# Spectacle_Button_Board.net
KiCad netlist of a schematic drawn in EAGLE
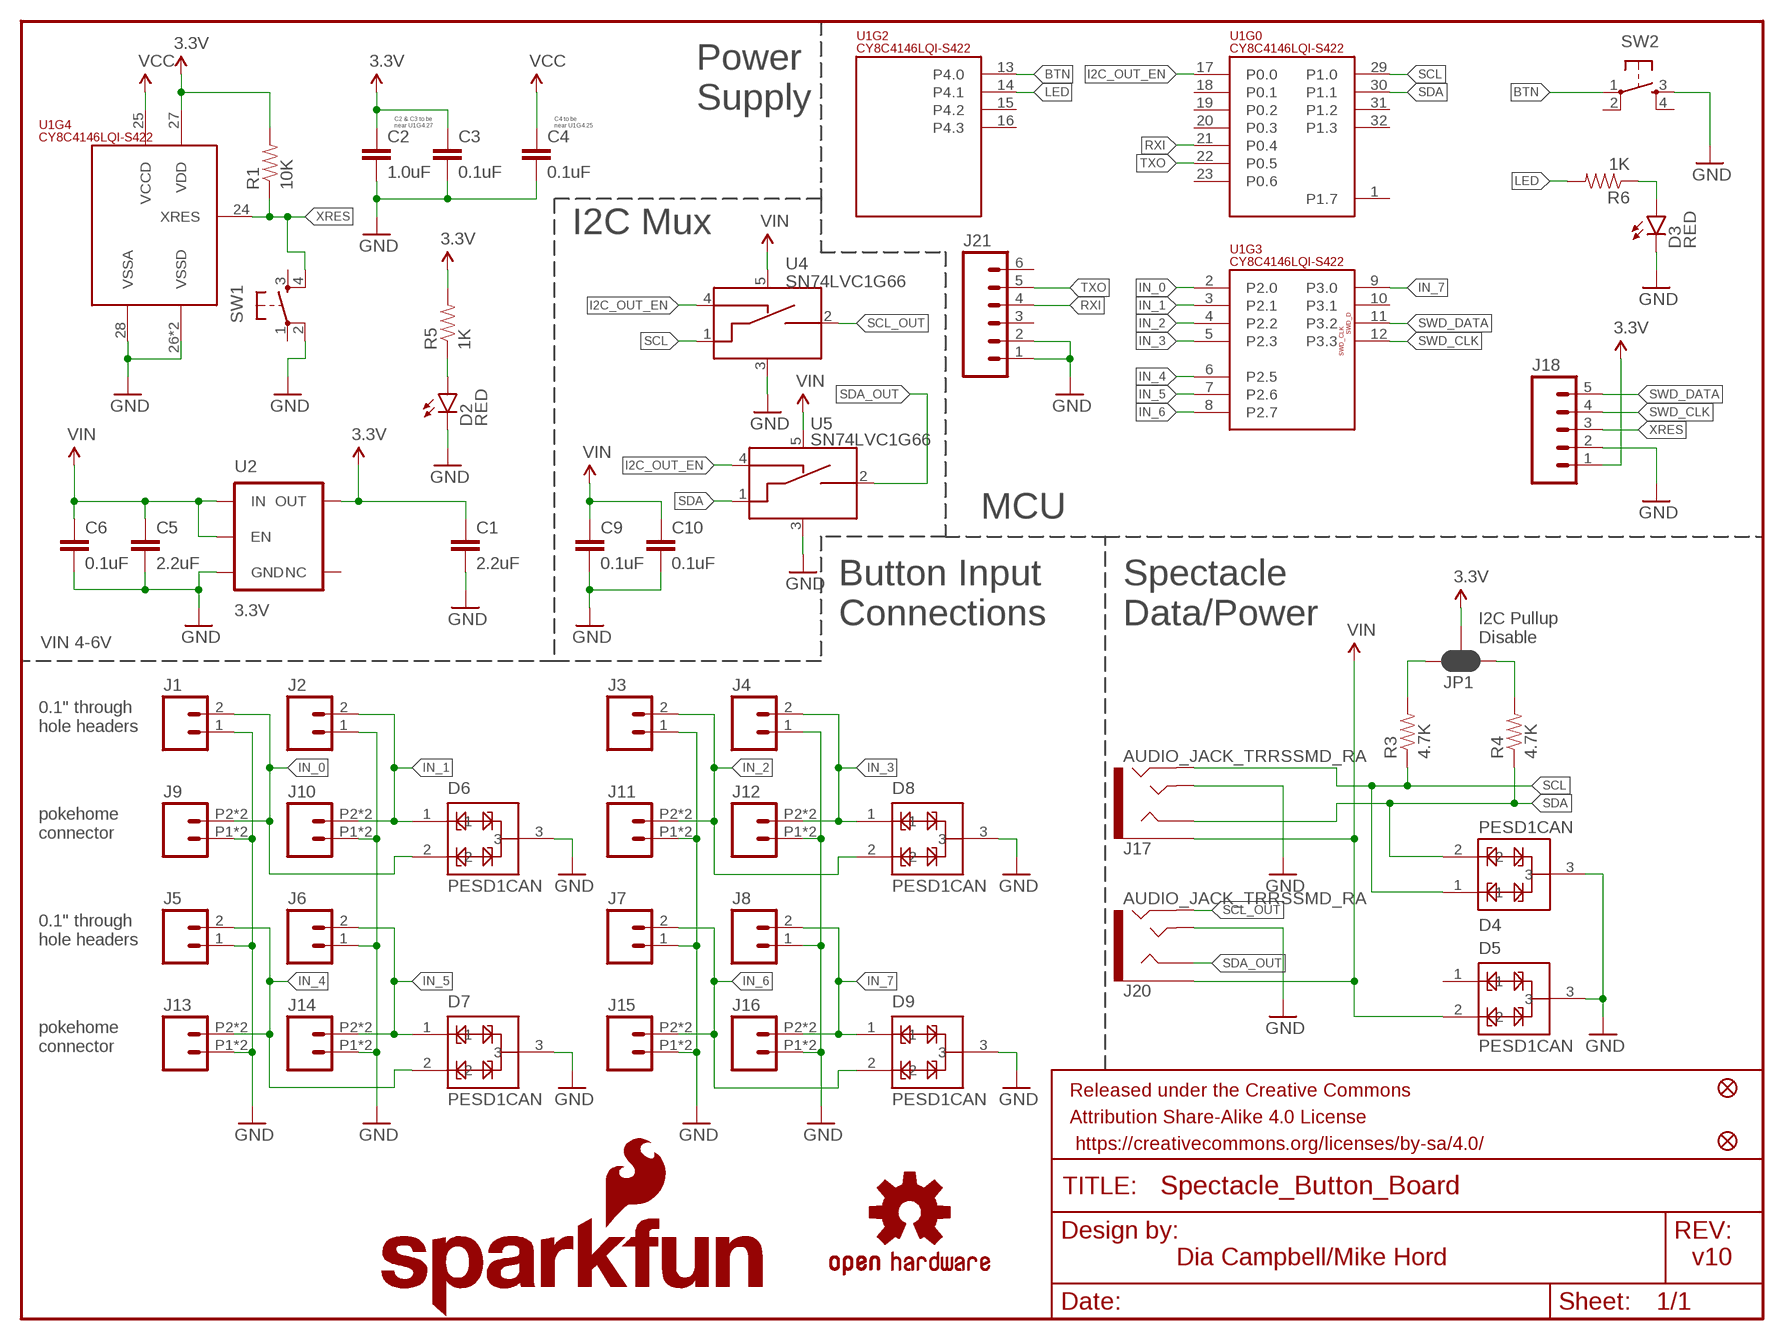
[diagram p0: schematic, sheet 1]

(export (version "E")
  (design (tool "Eeschema 10.0.6"))
  (components
    (comp (ref "C1")
      (value "2.2uF")
      (footprint "eagle-import:0603-CAP")
      (libsource (lib "eagle-import") (part "2.2UF-10V-20%(0603)"))
    )
    (comp (ref "C2")
      (value "1.0uF")
      (footprint "eagle-import:0402-CAP")
      (libsource (lib "eagle-import") (part "1.0UF-16V-10%(0402)"))
    )
    (comp (ref "C3")
      (value "0.1uF")
      (footprint "eagle-import:0402-CAP")
      (libsource (lib "eagle-import") (part "0.1UF-16V(+-10%)(0402)"))
    )
    (comp (ref "C4")
      (value "0.1uF")
      (footprint "eagle-import:0402-CAP")
      (libsource (lib "eagle-import") (part "0.1UF-16V(+-10%)(0402)"))
    )
    (comp (ref "C5")
      (value "2.2uF")
      (footprint "eagle-import:0603-CAP")
      (libsource (lib "eagle-import") (part "2.2UF-10V-20%(0603)"))
    )
    (comp (ref "C6")
      (value "0.1uF")
      (footprint "eagle-import:0402-CAP")
      (libsource (lib "eagle-import") (part "0.1UF-16V(+-10%)(0402)"))
    )
    (comp (ref "C9")
      (value "0.1uF")
      (footprint "eagle-import:0402-CAP")
      (libsource (lib "eagle-import") (part "0.1UF-16V(+-10%)(0402)"))
    )
    (comp (ref "C10")
      (value "0.1uF")
      (footprint "eagle-import:0402-CAP")
      (libsource (lib "eagle-import") (part "0.1UF-16V(+-10%)(0402)"))
    )
    (comp (ref "D2")
      (value "RED")
      (footprint "eagle-import:LED-0603")
      (libsource (lib "eagle-import") (part "LED-RED0603"))
    )
    (comp (ref "D3")
      (value "RED")
      (footprint "eagle-import:LED-0603")
      (libsource (lib "eagle-import") (part "LED-RED0603"))
    )
    (comp (ref "D4")
      (value "PESD1CAN")
      (footprint "eagle-import:SOT23-3")
      (libsource (lib "eagle-import") (part "PESD1CAN"))
    )
    (comp (ref "D5")
      (value "PESD1CAN")
      (footprint "eagle-import:SOT23-3")
      (libsource (lib "eagle-import") (part "PESD1CAN"))
    )
    (comp (ref "D6")
      (value "PESD1CAN")
      (footprint "eagle-import:SOT23-3")
      (libsource (lib "eagle-import") (part "PESD1CAN"))
    )
    (comp (ref "D7")
      (value "PESD1CAN")
      (footprint "eagle-import:SOT23-3")
      (libsource (lib "eagle-import") (part "PESD1CAN"))
    )
    (comp (ref "D8")
      (value "PESD1CAN")
      (footprint "eagle-import:SOT23-3")
      (libsource (lib "eagle-import") (part "PESD1CAN"))
    )
    (comp (ref "D9")
      (value "PESD1CAN")
      (footprint "eagle-import:SOT23-3")
      (libsource (lib "eagle-import") (part "PESD1CAN"))
    )
    (comp (ref "FD1")
      (value "FIDUCIALUFIDUCIAL")
      (footprint "eagle-import:MICRO-FIDUCIAL")
      (libsource (lib "eagle-import") (part "FIDUCIALUFIDUCIAL"))
    )
    (comp (ref "FD2")
      (value "FIDUCIALUFIDUCIAL")
      (footprint "eagle-import:MICRO-FIDUCIAL")
      (libsource (lib "eagle-import") (part "FIDUCIALUFIDUCIAL"))
    )
    (comp (ref "FRAME1")
      (value "FRAME-LETTER")
      (footprint "eagle-import:CREATIVE_COMMONS")
      (libsource (lib "eagle-import") (part "FRAME-LETTER"))
    )
    (comp (ref "J1")
      (value "M02PTH")
      (footprint "eagle-import:1X02")
      (libsource (lib "eagle-import") (part "M02PTH"))
    )
    (comp (ref "J2")
      (value "M02PTH")
      (footprint "eagle-import:1X02")
      (libsource (lib "eagle-import") (part "M02PTH"))
    )
    (comp (ref "J3")
      (value "M02PTH")
      (footprint "eagle-import:1X02")
      (libsource (lib "eagle-import") (part "M02PTH"))
    )
    (comp (ref "J4")
      (value "M02PTH")
      (footprint "eagle-import:1X02")
      (libsource (lib "eagle-import") (part "M02PTH"))
    )
    (comp (ref "J5")
      (value "M02PTH")
      (footprint "eagle-import:1X02")
      (libsource (lib "eagle-import") (part "M02PTH"))
    )
    (comp (ref "J6")
      (value "M02PTH")
      (footprint "eagle-import:1X02")
      (libsource (lib "eagle-import") (part "M02PTH"))
    )
    (comp (ref "J7")
      (value "M02PTH")
      (footprint "eagle-import:1X02")
      (libsource (lib "eagle-import") (part "M02PTH"))
    )
    (comp (ref "J8")
      (value "M02PTH")
      (footprint "eagle-import:1X02")
      (libsource (lib "eagle-import") (part "M02PTH"))
    )
    (comp (ref "J9")
      (value "M02SMALL_POKEHOME")
      (footprint "eagle-import:1X02_POKEHOME")
      (libsource (lib "eagle-import") (part "M02SMALL_POKEHOME"))
    )
    (comp (ref "J10")
      (value "M02SMALL_POKEHOME")
      (footprint "eagle-import:1X02_POKEHOME")
      (libsource (lib "eagle-import") (part "M02SMALL_POKEHOME"))
    )
    (comp (ref "J11")
      (value "M02SMALL_POKEHOME")
      (footprint "eagle-import:1X02_POKEHOME")
      (libsource (lib "eagle-import") (part "M02SMALL_POKEHOME"))
    )
    (comp (ref "J12")
      (value "M02SMALL_POKEHOME")
      (footprint "eagle-import:1X02_POKEHOME")
      (libsource (lib "eagle-import") (part "M02SMALL_POKEHOME"))
    )
    (comp (ref "J13")
      (value "M02SMALL_POKEHOME")
      (footprint "eagle-import:1X02_POKEHOME")
      (libsource (lib "eagle-import") (part "M02SMALL_POKEHOME"))
    )
    (comp (ref "J14")
      (value "M02SMALL_POKEHOME")
      (footprint "eagle-import:1X02_POKEHOME")
      (libsource (lib "eagle-import") (part "M02SMALL_POKEHOME"))
    )
    (comp (ref "J15")
      (value "M02SMALL_POKEHOME")
      (footprint "eagle-import:1X02_POKEHOME")
      (libsource (lib "eagle-import") (part "M02SMALL_POKEHOME"))
    )
    (comp (ref "J16")
      (value "M02SMALL_POKEHOME")
      (footprint "eagle-import:1X02_POKEHOME")
      (libsource (lib "eagle-import") (part "M02SMALL_POKEHOME"))
    )
    (comp (ref "J17")
      (value "AUDIO_JACK_TRRSSMD_RA")
      (footprint "eagle-import:AUDIO_JACK_3.5MM_TRRS_SMD_RA")
      (libsource (lib "eagle-import") (part "AUDIO_JACK_TRRSSMD_RA"))
    )
    (comp (ref "J18")
      (value "M05NO_SILK")
      (footprint "eagle-import:1X05_NO_SILK")
      (libsource (lib "eagle-import") (part "M05NO_SILK"))
    )
    (comp (ref "J20")
      (value "AUDIO_JACK_TRRSSMD_RA")
      (footprint "eagle-import:AUDIO_JACK_3.5MM_TRRS_SMD_RA")
      (libsource (lib "eagle-import") (part "AUDIO_JACK_TRRSSMD_RA"))
    )
    (comp (ref "J21")
      (value "M06NO_SILK_NO_POP")
      (footprint "eagle-import:1X06_NO_SILK")
      (libsource (lib "eagle-import") (part "M06NO_SILK_NO_POP"))
    )
    (comp (ref "JP1")
      (value "JUMPER-PAD-3-NC_BY_PASTE")
      (footprint "eagle-import:PAD-JUMPER-3-NC_BY_PASTE_YES_SILK_FULL_BOX")
      (libsource (lib "eagle-import") (part "JUMPER-PAD-3-NC_BY_PASTE"))
    )
    (comp (ref "LOGO1")
      (value "OSHW-LOGOM")
      (footprint "eagle-import:OSHW-LOGO-M")
      (libsource (lib "eagle-import") (part "OSHW-LOGOM"))
    )
    (comp (ref "LOGO2")
      (value "SFE_LOGO_NAME_FLAME.1_INCH")
      (footprint "eagle-import:SFE_LOGO_NAME_FLAME_.1")
      (libsource (lib "eagle-import") (part "SFE_LOGO_NAME_FLAME.1_INCH"))
    )
    (comp (ref "R1")
      (value "10K")
      (footprint "eagle-import:0603-RES")
      (libsource (lib "eagle-import") (part "10KOHM-1/10W-1%(0603)0603"))
    )
    (comp (ref "R3")
      (value "4.7K")
      (footprint "eagle-import:0603-RES")
      (libsource (lib "eagle-import") (part "4.7KOHM-1/10W-1%(0603)"))
    )
    (comp (ref "R4")
      (value "4.7K")
      (footprint "eagle-import:0603-RES")
      (libsource (lib "eagle-import") (part "4.7KOHM-1/10W-1%(0603)"))
    )
    (comp (ref "R5")
      (value "1K")
      (footprint "eagle-import:0603-RES")
      (libsource (lib "eagle-import") (part "1KOHM-1/10W-1%(0603)"))
    )
    (comp (ref "R6")
      (value "1K")
      (footprint "eagle-import:0603-RES")
      (libsource (lib "eagle-import") (part "1KOHM-1/10W-1%(0603)"))
    )
    (comp (ref "SW1")
      (value "SWITCH_SPST_4_PINRECT")
      (footprint "eagle-import:TACTILE_SWITCH_SMD_4.6X2.8MM")
      (libsource (lib "eagle-import") (part "SWITCH_SPST_4_PINRECT"))
    )
    (comp (ref "SW2")
      (value "SWITCH_SPST_4_PINRECT")
      (footprint "eagle-import:TACTILE_SWITCH_SMD_4.6X2.8MM")
      (libsource (lib "eagle-import") (part "SWITCH_SPST_4_PINRECT"))
    )
    (comp (ref "U1")
      (value "CY8C4146LQI-S422")
      (footprint "eagle-import:QFN-32")
      (libsource (lib "eagle-import") (part "PSOC4_4100S_32QFN"))
    )
    (comp (ref "U2")
      (value "3.3V")
      (footprint "eagle-import:SOT23-5")
      (libsource (lib "eagle-import") (part "V_REG_AP2112K-3.3V"))
    )
    (comp (ref "U4")
      (value "SN74LVC1G66")
      (footprint "eagle-import:SOT23-5")
      (libsource (lib "eagle-import") (part "SN74LVC1G66_SPST_AMUX"))
    )
    (comp (ref "U5")
      (value "SN74LVC1G66")
      (footprint "eagle-import:SOT23-5")
      (libsource (lib "eagle-import") (part "SN74LVC1G66_SPST_AMUX"))
    )
  )
  (nets
    (net (code "1") (name "3.3V") (class "Default")
      (node (ref "C1") (pin "1") (pinfunction "1_1") (pintype "passive"))
      (node (ref "C2") (pin "1") (pinfunction "1_1") (pintype "passive"))
      (node (ref "C3") (pin "1") (pinfunction "1_1") (pintype "passive"))
      (node (ref "J18") (pin "1") (pinfunction "1_1") (pintype "passive"))
      (node (ref "JP1") (pin "2") (pinfunction "2_2") (pintype "passive"))
      (node (ref "R1") (pin "2") (pinfunction "2_2") (pintype "passive"))
      (node (ref "R5") (pin "2") (pinfunction "2_2") (pintype "passive"))
      (node (ref "U1") (pin "27") (pinfunction "VDD_27") (pintype "bidirectional"))
      (node (ref "U2") (pin "5") (pinfunction "OUT_5") (pintype "passive"))
    )
    (net (code "2") (name "BTN") (class "Default")
      (node (ref "SW2") (pin "1") (pinfunction "1_1") (pintype "passive"))
      (node (ref "U1") (pin "13") (pinfunction "P4.0_13") (pintype "bidirectional"))
    )
    (net (code "3") (name "GND") (class "Default")
      (node (ref "C1") (pin "2") (pinfunction "2_2") (pintype "passive"))
      (node (ref "C10") (pin "2") (pinfunction "2_2") (pintype "passive"))
      (node (ref "C2") (pin "2") (pinfunction "2_2") (pintype "passive"))
      (node (ref "C3") (pin "2") (pinfunction "2_2") (pintype "passive"))
      (node (ref "C4") (pin "2") (pinfunction "2_2") (pintype "passive"))
      (node (ref "C5") (pin "2") (pinfunction "2_2") (pintype "passive"))
      (node (ref "C6") (pin "2") (pinfunction "2_2") (pintype "passive"))
      (node (ref "C9") (pin "2") (pinfunction "2_2") (pintype "passive"))
      (node (ref "D2") (pin "C") (pinfunction "C_C") (pintype "passive"))
      (node (ref "D3") (pin "C") (pinfunction "C_C") (pintype "passive"))
      (node (ref "D4") (pin "3") (pinfunction "3_3") (pintype "bidirectional"))
      (node (ref "D5") (pin "3") (pinfunction "3_3") (pintype "bidirectional"))
      (node (ref "D6") (pin "3") (pinfunction "3_3") (pintype "bidirectional"))
      (node (ref "D7") (pin "3") (pinfunction "3_3") (pintype "bidirectional"))
      (node (ref "D8") (pin "3") (pinfunction "3_3") (pintype "bidirectional"))
      (node (ref "D9") (pin "3") (pinfunction "3_3") (pintype "bidirectional"))
      (node (ref "J1") (pin "1") (pinfunction "1_1") (pintype "passive"))
      (node (ref "J10") (pin "P1") (pinfunction "1_P1") (pintype "passive"))
      (node (ref "J10") (pin "P3") (pinfunction "1_P3") (pintype "passive"))
      (node (ref "J11") (pin "P1") (pinfunction "1_P1") (pintype "passive"))
      (node (ref "J11") (pin "P3") (pinfunction "1_P3") (pintype "passive"))
      (node (ref "J12") (pin "P1") (pinfunction "1_P1") (pintype "passive"))
      (node (ref "J12") (pin "P3") (pinfunction "1_P3") (pintype "passive"))
      (node (ref "J13") (pin "P1") (pinfunction "1_P1") (pintype "passive"))
      (node (ref "J13") (pin "P3") (pinfunction "1_P3") (pintype "passive"))
      (node (ref "J14") (pin "P1") (pinfunction "1_P1") (pintype "passive"))
      (node (ref "J14") (pin "P3") (pinfunction "1_P3") (pintype "passive"))
      (node (ref "J15") (pin "P1") (pinfunction "1_P1") (pintype "passive"))
      (node (ref "J15") (pin "P3") (pinfunction "1_P3") (pintype "passive"))
      (node (ref "J16") (pin "P1") (pinfunction "1_P1") (pintype "passive"))
      (node (ref "J16") (pin "P3") (pinfunction "1_P3") (pintype "passive"))
      (node (ref "J17") (pin "TIP") (pinfunction "TIP_TIP") (pintype "bidirectional"))
      (node (ref "J18") (pin "2") (pinfunction "2_2") (pintype "passive"))
      (node (ref "J2") (pin "1") (pinfunction "1_1") (pintype "passive"))
      (node (ref "J20") (pin "TIP") (pinfunction "TIP_TIP") (pintype "bidirectional"))
      (node (ref "J21") (pin "1") (pinfunction "1_1") (pintype "passive"))
      (node (ref "J21") (pin "2") (pinfunction "2_2") (pintype "passive"))
      (node (ref "J3") (pin "1") (pinfunction "1_1") (pintype "passive"))
      (node (ref "J4") (pin "1") (pinfunction "1_1") (pintype "passive"))
      (node (ref "J5") (pin "1") (pinfunction "1_1") (pintype "passive"))
      (node (ref "J6") (pin "1") (pinfunction "1_1") (pintype "passive"))
      (node (ref "J7") (pin "1") (pinfunction "1_1") (pintype "passive"))
      (node (ref "J8") (pin "1") (pinfunction "1_1") (pintype "passive"))
      (node (ref "J9") (pin "P1") (pinfunction "1_P1") (pintype "passive"))
      (node (ref "J9") (pin "P3") (pinfunction "1_P3") (pintype "passive"))
      (node (ref "SW1") (pin "2") (pinfunction "2_2") (pintype "passive"))
      (node (ref "SW2") (pin "3") (pinfunction "3_3") (pintype "passive"))
      (node (ref "U1") (pin "26") (pinfunction "VSSD_26") (pintype "bidirectional"))
      (node (ref "U1") (pin "28") (pinfunction "VSSA_28") (pintype "bidirectional"))
      (node (ref "U1") (pin "EP") (pinfunction "VSSD_EP") (pintype "bidirectional"))
      (node (ref "U2") (pin "2") (pinfunction "GND_2") (pintype "input"))
      (node (ref "U4") (pin "3") (pinfunction "VSS_3") (pintype "bidirectional"))
      (node (ref "U5") (pin "3") (pinfunction "VSS_3") (pintype "bidirectional"))
    )
    (net (code "4") (name "I2C_OUT_EN") (class "Default")
      (node (ref "U1") (pin "17") (pinfunction "P0.0_17") (pintype "bidirectional"))
      (node (ref "U4") (pin "4") (pinfunction "CTRL_IN_4") (pintype "bidirectional"))
      (node (ref "U5") (pin "4") (pinfunction "CTRL_IN_4") (pintype "bidirectional"))
    )
    (net (code "5") (name "IN_0") (class "Default")
      (node (ref "D6") (pin "2") (pinfunction "2_2") (pintype "bidirectional"))
      (node (ref "J1") (pin "2") (pinfunction "2_2") (pintype "passive"))
      (node (ref "J9") (pin "P2") (pinfunction "2_P2") (pintype "passive"))
      (node (ref "J9") (pin "P4") (pinfunction "2_P4") (pintype "passive"))
      (node (ref "U1") (pin "2") (pinfunction "P2.0_2") (pintype "bidirectional"))
    )
    (net (code "6") (name "IN_1") (class "Default")
      (node (ref "D6") (pin "1") (pinfunction "1_1") (pintype "bidirectional"))
      (node (ref "J10") (pin "P2") (pinfunction "2_P2") (pintype "passive"))
      (node (ref "J10") (pin "P4") (pinfunction "2_P4") (pintype "passive"))
      (node (ref "J2") (pin "2") (pinfunction "2_2") (pintype "passive"))
      (node (ref "U1") (pin "3") (pinfunction "P2.1_3") (pintype "bidirectional"))
    )
    (net (code "7") (name "IN_2") (class "Default")
      (node (ref "D8") (pin "2") (pinfunction "2_2") (pintype "bidirectional"))
      (node (ref "J11") (pin "P2") (pinfunction "2_P2") (pintype "passive"))
      (node (ref "J11") (pin "P4") (pinfunction "2_P4") (pintype "passive"))
      (node (ref "J3") (pin "2") (pinfunction "2_2") (pintype "passive"))
      (node (ref "U1") (pin "4") (pinfunction "P2.2_4") (pintype "bidirectional"))
    )
    (net (code "8") (name "IN_3") (class "Default")
      (node (ref "D8") (pin "1") (pinfunction "1_1") (pintype "bidirectional"))
      (node (ref "J12") (pin "P2") (pinfunction "2_P2") (pintype "passive"))
      (node (ref "J12") (pin "P4") (pinfunction "2_P4") (pintype "passive"))
      (node (ref "J4") (pin "2") (pinfunction "2_2") (pintype "passive"))
      (node (ref "U1") (pin "5") (pinfunction "P2.3_5") (pintype "bidirectional"))
    )
    (net (code "9") (name "IN_4") (class "Default")
      (node (ref "D7") (pin "2") (pinfunction "2_2") (pintype "bidirectional"))
      (node (ref "J13") (pin "P2") (pinfunction "2_P2") (pintype "passive"))
      (node (ref "J13") (pin "P4") (pinfunction "2_P4") (pintype "passive"))
      (node (ref "J5") (pin "2") (pinfunction "2_2") (pintype "passive"))
      (node (ref "U1") (pin "6") (pinfunction "P2.5_6") (pintype "bidirectional"))
    )
    (net (code "10") (name "IN_5") (class "Default")
      (node (ref "D7") (pin "1") (pinfunction "1_1") (pintype "bidirectional"))
      (node (ref "J14") (pin "P2") (pinfunction "2_P2") (pintype "passive"))
      (node (ref "J14") (pin "P4") (pinfunction "2_P4") (pintype "passive"))
      (node (ref "J6") (pin "2") (pinfunction "2_2") (pintype "passive"))
      (node (ref "U1") (pin "7") (pinfunction "P2.6_7") (pintype "bidirectional"))
    )
    (net (code "11") (name "IN_6") (class "Default")
      (node (ref "D9") (pin "2") (pinfunction "2_2") (pintype "bidirectional"))
      (node (ref "J15") (pin "P2") (pinfunction "2_P2") (pintype "passive"))
      (node (ref "J15") (pin "P4") (pinfunction "2_P4") (pintype "passive"))
      (node (ref "J7") (pin "2") (pinfunction "2_2") (pintype "passive"))
      (node (ref "U1") (pin "8") (pinfunction "P2.7_8") (pintype "bidirectional"))
    )
    (net (code "12") (name "IN_7") (class "Default")
      (node (ref "D9") (pin "1") (pinfunction "1_1") (pintype "bidirectional"))
      (node (ref "J16") (pin "P2") (pinfunction "2_P2") (pintype "passive"))
      (node (ref "J16") (pin "P4") (pinfunction "2_P4") (pintype "passive"))
      (node (ref "J8") (pin "2") (pinfunction "2_2") (pintype "passive"))
      (node (ref "U1") (pin "9") (pinfunction "P3.0_9") (pintype "bidirectional"))
    )
    (net (code "13") (name "LED") (class "Default")
      (node (ref "R6") (pin "2") (pinfunction "2_2") (pintype "passive"))
      (node (ref "U1") (pin "14") (pinfunction "P4.1_14") (pintype "bidirectional"))
    )
    (net (code "14") (name "Net-(D2-PadA)") (class "Default")
      (node (ref "D2") (pin "A") (pinfunction "A_A") (pintype "passive"))
      (node (ref "R5") (pin "1") (pinfunction "1_1") (pintype "passive"))
    )
    (net (code "15") (name "Net-(D3-PadA)") (class "Default")
      (node (ref "D3") (pin "A") (pinfunction "A_A") (pintype "passive"))
      (node (ref "R6") (pin "1") (pinfunction "1_1") (pintype "passive"))
    )
    (net (code "16") (name "Net-(JP1-Pad1)") (class "Default")
      (node (ref "JP1") (pin "1") (pinfunction "1_1") (pintype "passive"))
      (node (ref "R4") (pin "2") (pinfunction "2_2") (pintype "passive"))
    )
    (net (code "17") (name "Net-(JP1-Pad3)") (class "Default")
      (node (ref "JP1") (pin "3") (pinfunction "3_3") (pintype "passive"))
      (node (ref "R3") (pin "2") (pinfunction "2_2") (pintype "passive"))
    )
    (net (code "18") (name "RXI") (class "Default")
      (node (ref "J21") (pin "4") (pinfunction "4_4") (pintype "passive"))
      (node (ref "U1") (pin "21") (pinfunction "P0.4_21") (pintype "bidirectional"))
    )
    (net (code "19") (name "SCL") (class "Default")
      (node (ref "D4") (pin "1") (pinfunction "1_1") (pintype "bidirectional"))
      (node (ref "J17") (pin "RING2") (pinfunction "RING2_RING2") (pintype "bidirectional"))
      (node (ref "R3") (pin "1") (pinfunction "1_1") (pintype "passive"))
      (node (ref "U1") (pin "29") (pinfunction "P1.0_29") (pintype "bidirectional"))
      (node (ref "U4") (pin "1") (pinfunction "A_IN_1") (pintype "bidirectional"))
    )
    (net (code "20") (name "SCL_OUT") (class "Default")
      (node (ref "J20") (pin "RING2") (pinfunction "RING2_RING2") (pintype "bidirectional"))
      (node (ref "U4") (pin "2") (pinfunction "A_OUT_2") (pintype "bidirectional"))
    )
    (net (code "21") (name "SDA") (class "Default")
      (node (ref "D4") (pin "2") (pinfunction "2_2") (pintype "bidirectional"))
      (node (ref "J17") (pin "RING1") (pinfunction "RING1_RING1") (pintype "bidirectional"))
      (node (ref "R4") (pin "1") (pinfunction "1_1") (pintype "passive"))
      (node (ref "U1") (pin "30") (pinfunction "P1.1_30") (pintype "bidirectional"))
      (node (ref "U5") (pin "1") (pinfunction "A_IN_1") (pintype "bidirectional"))
    )
    (net (code "22") (name "SDA_OUT") (class "Default")
      (node (ref "J20") (pin "RING1") (pinfunction "RING1_RING1") (pintype "bidirectional"))
      (node (ref "U5") (pin "2") (pinfunction "A_OUT_2") (pintype "bidirectional"))
    )
    (net (code "23") (name "SWD_CLK") (class "Default")
      (node (ref "J18") (pin "4") (pinfunction "4_4") (pintype "passive"))
      (node (ref "U1") (pin "12") (pinfunction "P3.3_12") (pintype "bidirectional"))
    )
    (net (code "24") (name "SWD_DATA") (class "Default")
      (node (ref "J18") (pin "5") (pinfunction "5_5") (pintype "passive"))
      (node (ref "U1") (pin "11") (pinfunction "P3.2_11") (pintype "bidirectional"))
    )
    (net (code "25") (name "TXO") (class "Default")
      (node (ref "J21") (pin "5") (pinfunction "5_5") (pintype "passive"))
      (node (ref "U1") (pin "22") (pinfunction "P0.5_22") (pintype "bidirectional"))
    )
    (net (code "26") (name "VCC") (class "Default")
      (node (ref "C4") (pin "1") (pinfunction "1_1") (pintype "passive"))
      (node (ref "U1") (pin "25") (pinfunction "VCCD_25") (pintype "bidirectional"))
    )
    (net (code "27") (name "VIN") (class "Default")
      (node (ref "C10") (pin "1") (pinfunction "1_1") (pintype "passive"))
      (node (ref "C5") (pin "1") (pinfunction "1_1") (pintype "passive"))
      (node (ref "C6") (pin "1") (pinfunction "1_1") (pintype "passive"))
      (node (ref "C9") (pin "1") (pinfunction "1_1") (pintype "passive"))
      (node (ref "D5") (pin "2") (pinfunction "2_2") (pintype "bidirectional"))
      (node (ref "J17") (pin "EARTH") (pinfunction "EARTH_EARTH") (pintype "bidirectional"))
      (node (ref "J20") (pin "EARTH") (pinfunction "EARTH_EARTH") (pintype "bidirectional"))
      (node (ref "U2") (pin "1") (pinfunction "IN_1") (pintype "input"))
      (node (ref "U2") (pin "3") (pinfunction "EN_3") (pintype "input"))
      (node (ref "U4") (pin "5") (pinfunction "VCC_5") (pintype "bidirectional"))
      (node (ref "U5") (pin "5") (pinfunction "VCC_5") (pintype "bidirectional"))
    )
    (net (code "28") (name "XRES") (class "Default")
      (node (ref "J18") (pin "3") (pinfunction "3_3") (pintype "passive"))
      (node (ref "R1") (pin "1") (pinfunction "1_1") (pintype "passive"))
      (node (ref "SW1") (pin "4") (pinfunction "4_4") (pintype "passive"))
      (node (ref "U1") (pin "24") (pinfunction "XRES_24") (pintype "bidirectional"))
    )
    (net (code "29") (name "unconnected-(D5-Pad1)") (class "Default")
      (node (ref "D5") (pin "1") (pinfunction "1_1") (pintype "bidirectional"))
    )
    (net (code "30") (name "unconnected-(J21-Pad3)") (class "Default")
      (node (ref "J21") (pin "3") (pinfunction "3_3") (pintype "passive"))
    )
    (net (code "31") (name "unconnected-(J21-Pad6)") (class "Default")
      (node (ref "J21") (pin "6") (pinfunction "6_6") (pintype "passive"))
    )
    (net (code "32") (name "unconnected-(SW1-Pad1)") (class "Default")
      (node (ref "SW1") (pin "1") (pinfunction "1_1") (pintype "passive"))
    )
    (net (code "33") (name "unconnected-(SW1-Pad3)") (class "Default")
      (node (ref "SW1") (pin "3") (pinfunction "3_3") (pintype "passive"))
    )
    (net (code "34") (name "unconnected-(SW2-Pad2)") (class "Default")
      (node (ref "SW2") (pin "2") (pinfunction "2_2") (pintype "passive"))
    )
    (net (code "35") (name "unconnected-(SW2-Pad4)") (class "Default")
      (node (ref "SW2") (pin "4") (pinfunction "4_4") (pintype "passive"))
    )
    (net (code "36") (name "unconnected-(U1A-P0.1-Pad18)") (class "Default")
      (node (ref "U1") (pin "18") (pinfunction "P0.1_18") (pintype "bidirectional"))
    )
    (net (code "37") (name "unconnected-(U1A-P0.2-Pad19)") (class "Default")
      (node (ref "U1") (pin "19") (pinfunction "P0.2_19") (pintype "bidirectional"))
    )
    (net (code "38") (name "unconnected-(U1A-P0.3-Pad20)") (class "Default")
      (node (ref "U1") (pin "20") (pinfunction "P0.3_20") (pintype "bidirectional"))
    )
    (net (code "39") (name "unconnected-(U1A-P0.6-Pad23)") (class "Default")
      (node (ref "U1") (pin "23") (pinfunction "P0.6_23") (pintype "bidirectional"))
    )
    (net (code "40") (name "unconnected-(U1A-P1.2-Pad31)") (class "Default")
      (node (ref "U1") (pin "31") (pinfunction "P1.2_31") (pintype "bidirectional"))
    )
    (net (code "41") (name "unconnected-(U1A-P1.3-Pad32)") (class "Default")
      (node (ref "U1") (pin "32") (pinfunction "P1.3_32") (pintype "bidirectional"))
    )
    (net (code "42") (name "unconnected-(U1A-P1.7-Pad1)") (class "Default")
      (node (ref "U1") (pin "1") (pinfunction "P1.7_1") (pintype "bidirectional"))
    )
    (net (code "43") (name "unconnected-(U1B-P4.2-Pad15)") (class "Default")
      (node (ref "U1") (pin "15") (pinfunction "P4.2_15") (pintype "bidirectional"))
    )
    (net (code "44") (name "unconnected-(U1B-P4.3-Pad16)") (class "Default")
      (node (ref "U1") (pin "16") (pinfunction "P4.3_16") (pintype "bidirectional"))
    )
    (net (code "45") (name "unconnected-(U1C-P3.1-Pad10)") (class "Default")
      (node (ref "U1") (pin "10") (pinfunction "P3.1_10") (pintype "bidirectional"))
    )
    (net (code "46") (name "unconnected-(U2-NC-Pad4)") (class "Default")
      (node (ref "U2") (pin "4") (pinfunction "NC_4") (pintype "input"))
    )
  )
)
